# sensor_wifi.net
KiCad netlist of a schematic drawn in Altium Designer
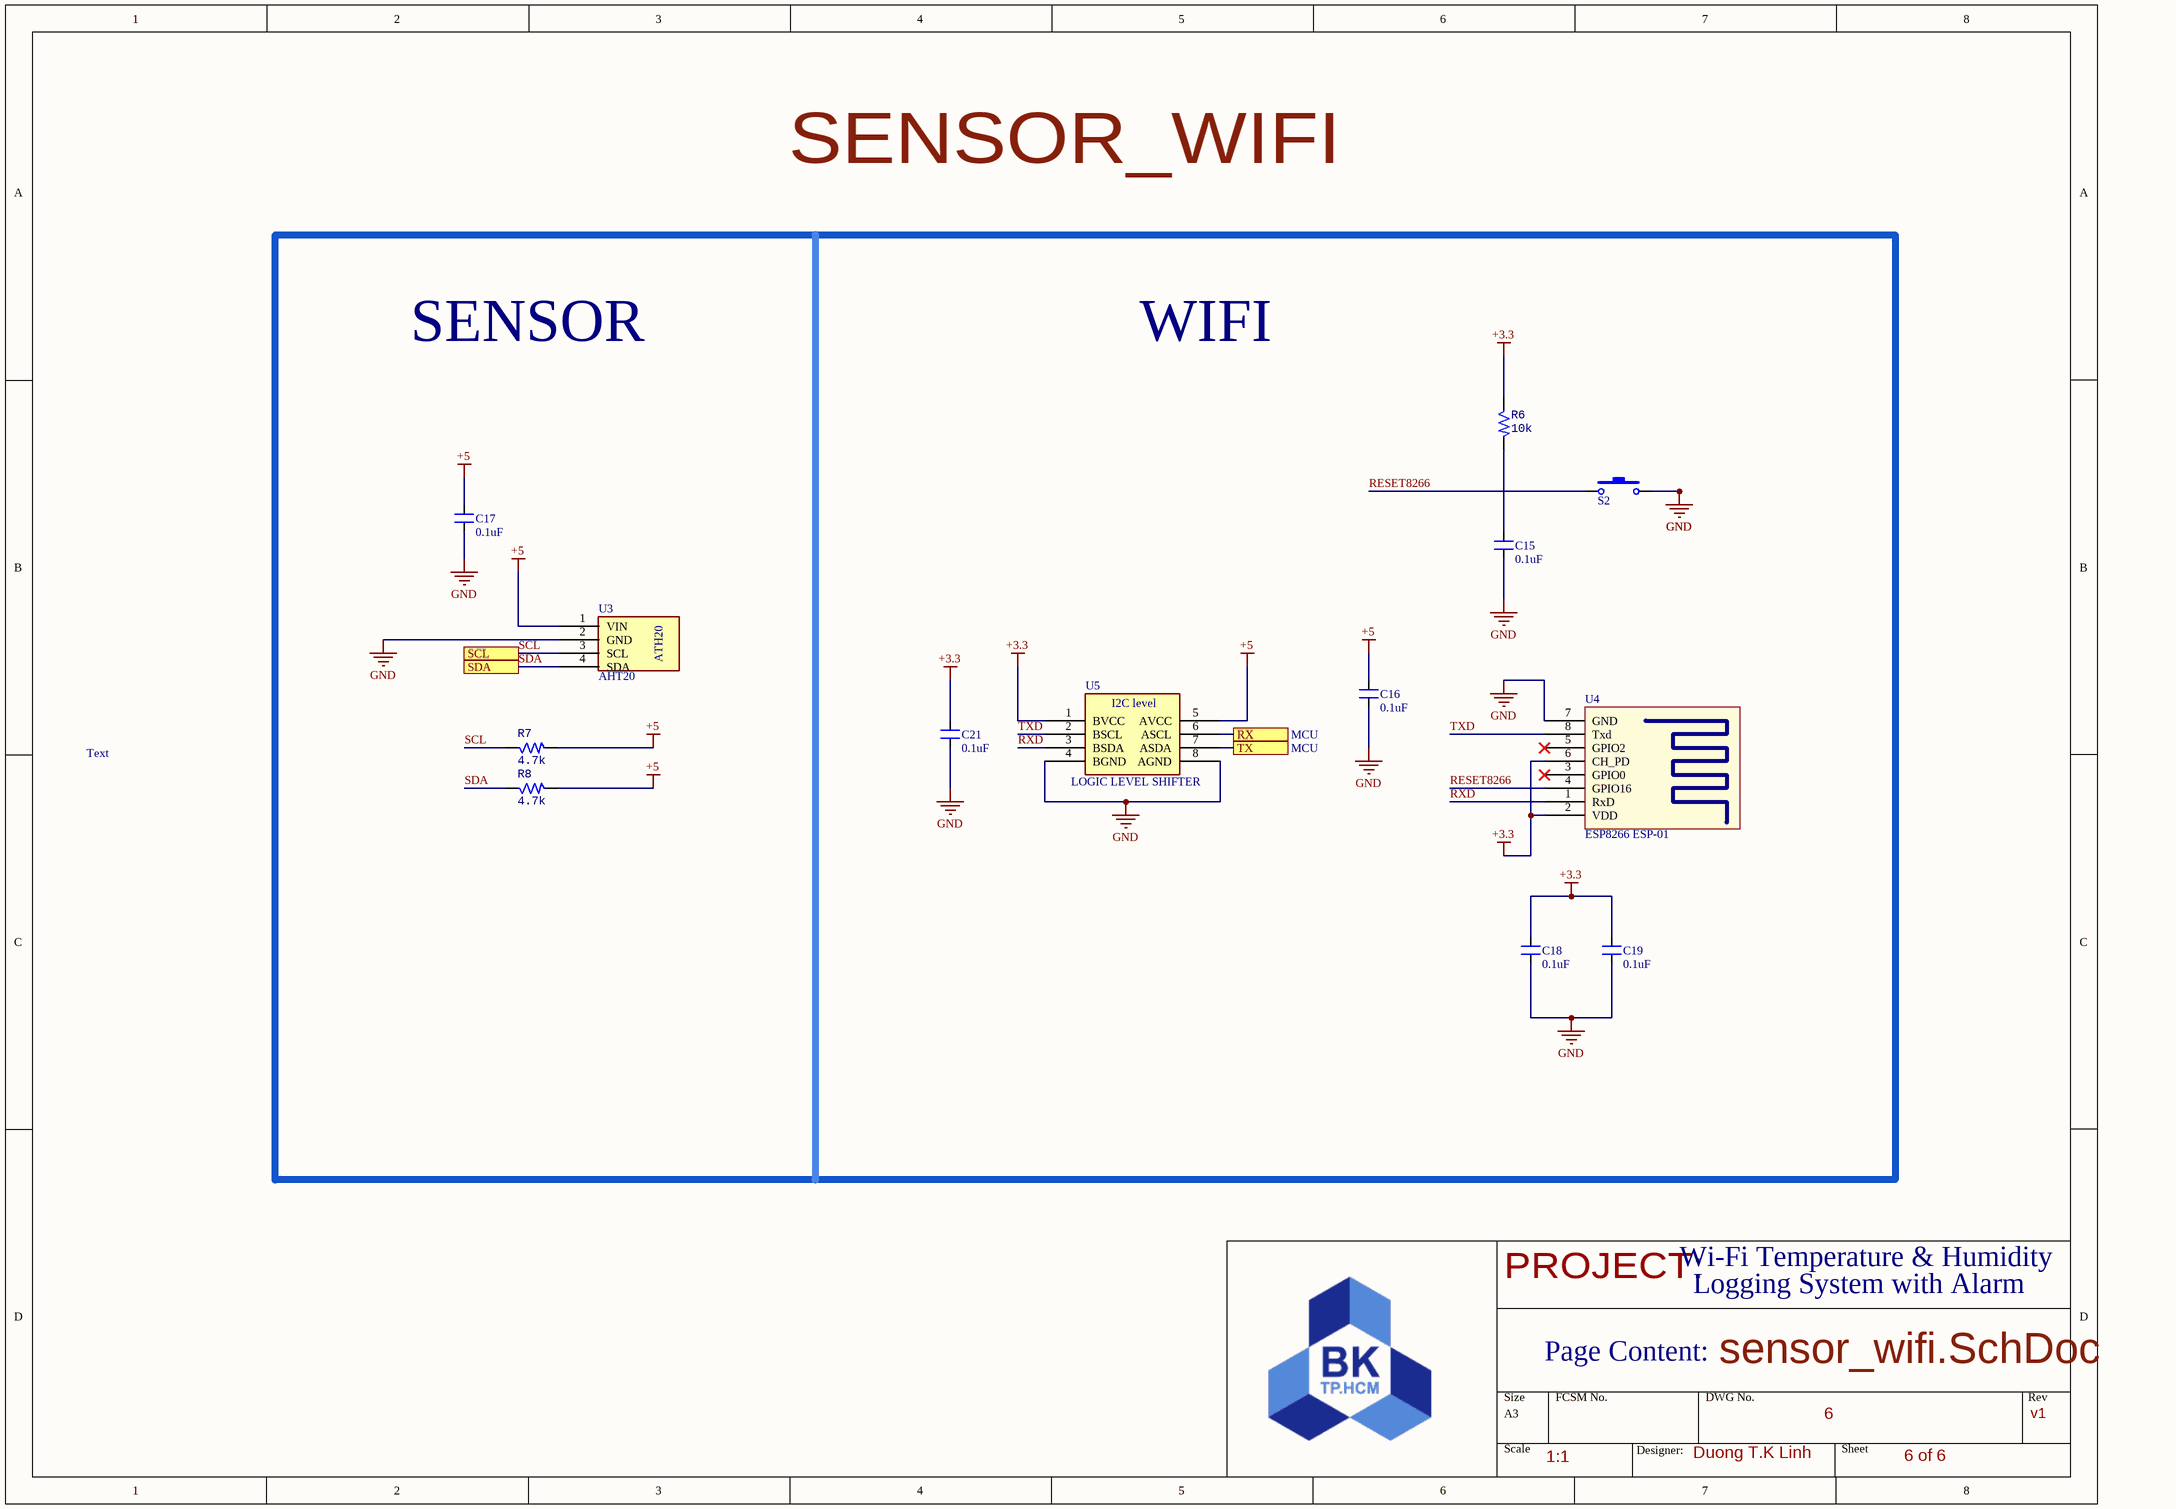
[diagram p0: sensor_wifi.SchDoc]

(export (version "E")
  (design (tool "Eeschema 10.0.6"))
  (components
    (comp (ref "C15")
      (value "0.1uF")
      (footprint "CN2")
      (description "Cap np 104 => 105pF")
      (libsource (lib "Compiled_Devzone") (part "CN2"))
    )
    (comp (ref "C16")
      (value "0.1uF")
      (footprint "CN2")
      (description "Cap np 104 => 105pF")
      (libsource (lib "Compiled_Devzone") (part "CN2"))
    )
    (comp (ref "C17")
      (value "0.1uF")
      (footprint "CN2")
      (description "Cap np 104 => 105pF")
      (libsource (lib "Compiled_Devzone") (part "CN2"))
    )
    (comp (ref "C18")
      (value "0.1uF")
      (footprint "CN2")
      (description "Cap np 104 => 105pF")
      (libsource (lib "Compiled_Devzone") (part "CN2"))
    )
    (comp (ref "C19")
      (value "0.1uF")
      (footprint "CN2")
      (description "Cap np 104 => 105pF")
      (libsource (lib "Compiled_Devzone") (part "CN2"))
    )
    (comp (ref "C21")
      (value "0.1uF")
      (footprint "CN2")
      (description "Cap np 104 => 105pF")
      (libsource (lib "Compiled_Devzone") (part "CN2"))
    )
    (comp (ref "R6") (value "10k") (footprint "RES-1/4W-SMALL") (libsource (lib "ID") (part "RES-SMD")))
    (comp (ref "R7") (value "4.7k") (footprint "RES-1/4W-SMALL") (libsource (lib "ID") (part "RES-SMD")))
    (comp (ref "R8") (value "4.7k") (footprint "RES-1/4W-SMALL") (libsource (lib "ID") (part "RES-SMD")))
    (comp (ref "S2")
      (value "RESET_WIFI")
      (footprint "BUTTON  ROUND")
      (description "Switch-Button")
      (fields (field (name "PUBLISHER") "Altium Limited"))
      (libsource (lib "KhanhBK_Library_4") (part "SW-Button"))
    )
    (comp (ref "U3") (value "AHT20") (footprint "AHT20") (libsource (lib "Schlib1") (part "ATH20")))
    (comp (ref "U4")
      (value "ESP8266 ESP-01")
      (footprint "ESP8266 ESP-01")
      (libsource (lib "KhanhBK_Library_4") (part "ESP8266 ESP-01"))
    )
    (comp (ref "U5")
      (value "LOGIC LEVEL SHIFTER")
      (footprint "I2C LEVEL")
      (libsource (lib "Schlib1") (part "i2c level"))
    )
  )
  (nets
    (net (code "1") (name "+3.3") (class "Default")
      (node (ref "C18") (pin "2") (pinfunction "2_2") (pintype "passive"))
      (node (ref "C19") (pin "2") (pinfunction "2_2") (pintype "passive"))
      (node (ref "C21") (pin "2") (pinfunction "2_2") (pintype "passive"))
      (node (ref "R6") (pin "1") (pinfunction "1_1") (pintype "passive"))
      (node (ref "U4") (pin "2") (pinfunction "VDD_2") (pintype "passive"))
      (node (ref "U4") (pin "6") (pinfunction "CH_PD_6") (pintype "passive"))
      (node (ref "U5") (pin "1") (pinfunction "BVCC_1") (pintype "passive"))
    )
    (net (code "2") (name "+5") (class "Default")
      (node (ref "C16") (pin "2") (pinfunction "2_2") (pintype "passive"))
      (node (ref "C17") (pin "2") (pinfunction "2_2") (pintype "passive"))
      (node (ref "R7") (pin "2") (pinfunction "2_2") (pintype "passive"))
      (node (ref "R8") (pin "2") (pinfunction "2_2") (pintype "passive"))
      (node (ref "U3") (pin "1") (pinfunction "VIN_1") (pintype "passive"))
      (node (ref "U5") (pin "5") (pinfunction "AVCC_5") (pintype "passive"))
    )
    (net (code "3") (name "/RESET8266") (class "Default")
      (node (ref "S2") (pin "1") (pinfunction "1_1") (pintype "passive"))
      (node (ref "U4") (pin "4") (pinfunction "GPIO16_4") (pintype "passive"))
    )
    (net (code "4") (name "/RX") (class "Default")
      (node (ref "U5") (pin "6") (pinfunction "ASCL_6") (pintype "passive"))
    )
    (net (code "5") (name "/RXD") (class "Default")
      (node (ref "U4") (pin "1") (pinfunction "RxD_1") (pintype "passive"))
      (node (ref "U5") (pin "3") (pinfunction "BSDA_3") (pintype "passive"))
    )
    (net (code "6") (name "/SCL") (class "Default")
      (node (ref "R7") (pin "1") (pinfunction "1_1") (pintype "passive"))
      (node (ref "U3") (pin "3") (pinfunction "SCL_3") (pintype "passive"))
    )
    (net (code "7") (name "/SDA") (class "Default")
      (node (ref "R8") (pin "1") (pinfunction "1_1") (pintype "passive"))
      (node (ref "U3") (pin "4") (pinfunction "SDA_4") (pintype "passive"))
    )
    (net (code "8") (name "/TX") (class "Default")
      (node (ref "U5") (pin "7") (pinfunction "ASDA_7") (pintype "passive"))
    )
    (net (code "9") (name "/TXD") (class "Default")
      (node (ref "U4") (pin "8") (pinfunction "Txd_8") (pintype "passive"))
      (node (ref "U5") (pin "2") (pinfunction "BSCL_2") (pintype "passive"))
    )
    (net (code "10") (name "GND") (class "Default")
      (node (ref "C15") (pin "1") (pinfunction "1_1") (pintype "passive"))
      (node (ref "C16") (pin "1") (pinfunction "1_1") (pintype "passive"))
      (node (ref "C17") (pin "1") (pinfunction "1_1") (pintype "passive"))
      (node (ref "C18") (pin "1") (pinfunction "1_1") (pintype "passive"))
      (node (ref "C19") (pin "1") (pinfunction "1_1") (pintype "passive"))
      (node (ref "C21") (pin "1") (pinfunction "1_1") (pintype "passive"))
      (node (ref "S2") (pin "2") (pinfunction "2_2") (pintype "passive"))
      (node (ref "U3") (pin "2") (pinfunction "GND_2") (pintype "passive"))
      (node (ref "U4") (pin "7") (pinfunction "GND_7") (pintype "passive"))
      (node (ref "U5") (pin "4") (pinfunction "BGND_4") (pintype "passive"))
      (node (ref "U5") (pin "8") (pinfunction "AGND_8") (pintype "passive"))
    )
    (net (code "11") (name "Net-(C15-Pad2)") (class "Default")
      (node (ref "C15") (pin "2") (pinfunction "2_2") (pintype "passive"))
      (node (ref "R6") (pin "2") (pinfunction "2_2") (pintype "passive"))
    )
    (net (code "12") (name "unconnected-(U4-GPIO0-Pad3)") (class "Default")
      (node (ref "U4") (pin "3") (pinfunction "GPIO0_3") (pintype "passive+no_connect"))
    )
    (net (code "13") (name "unconnected-(U4-GPIO2-Pad5)") (class "Default")
      (node (ref "U4") (pin "5") (pinfunction "GPIO2_5") (pintype "passive+no_connect"))
    )
  )
)
